# USB_Audio_Interface.net
KiCad netlist of a schematic drawn in EAGLE
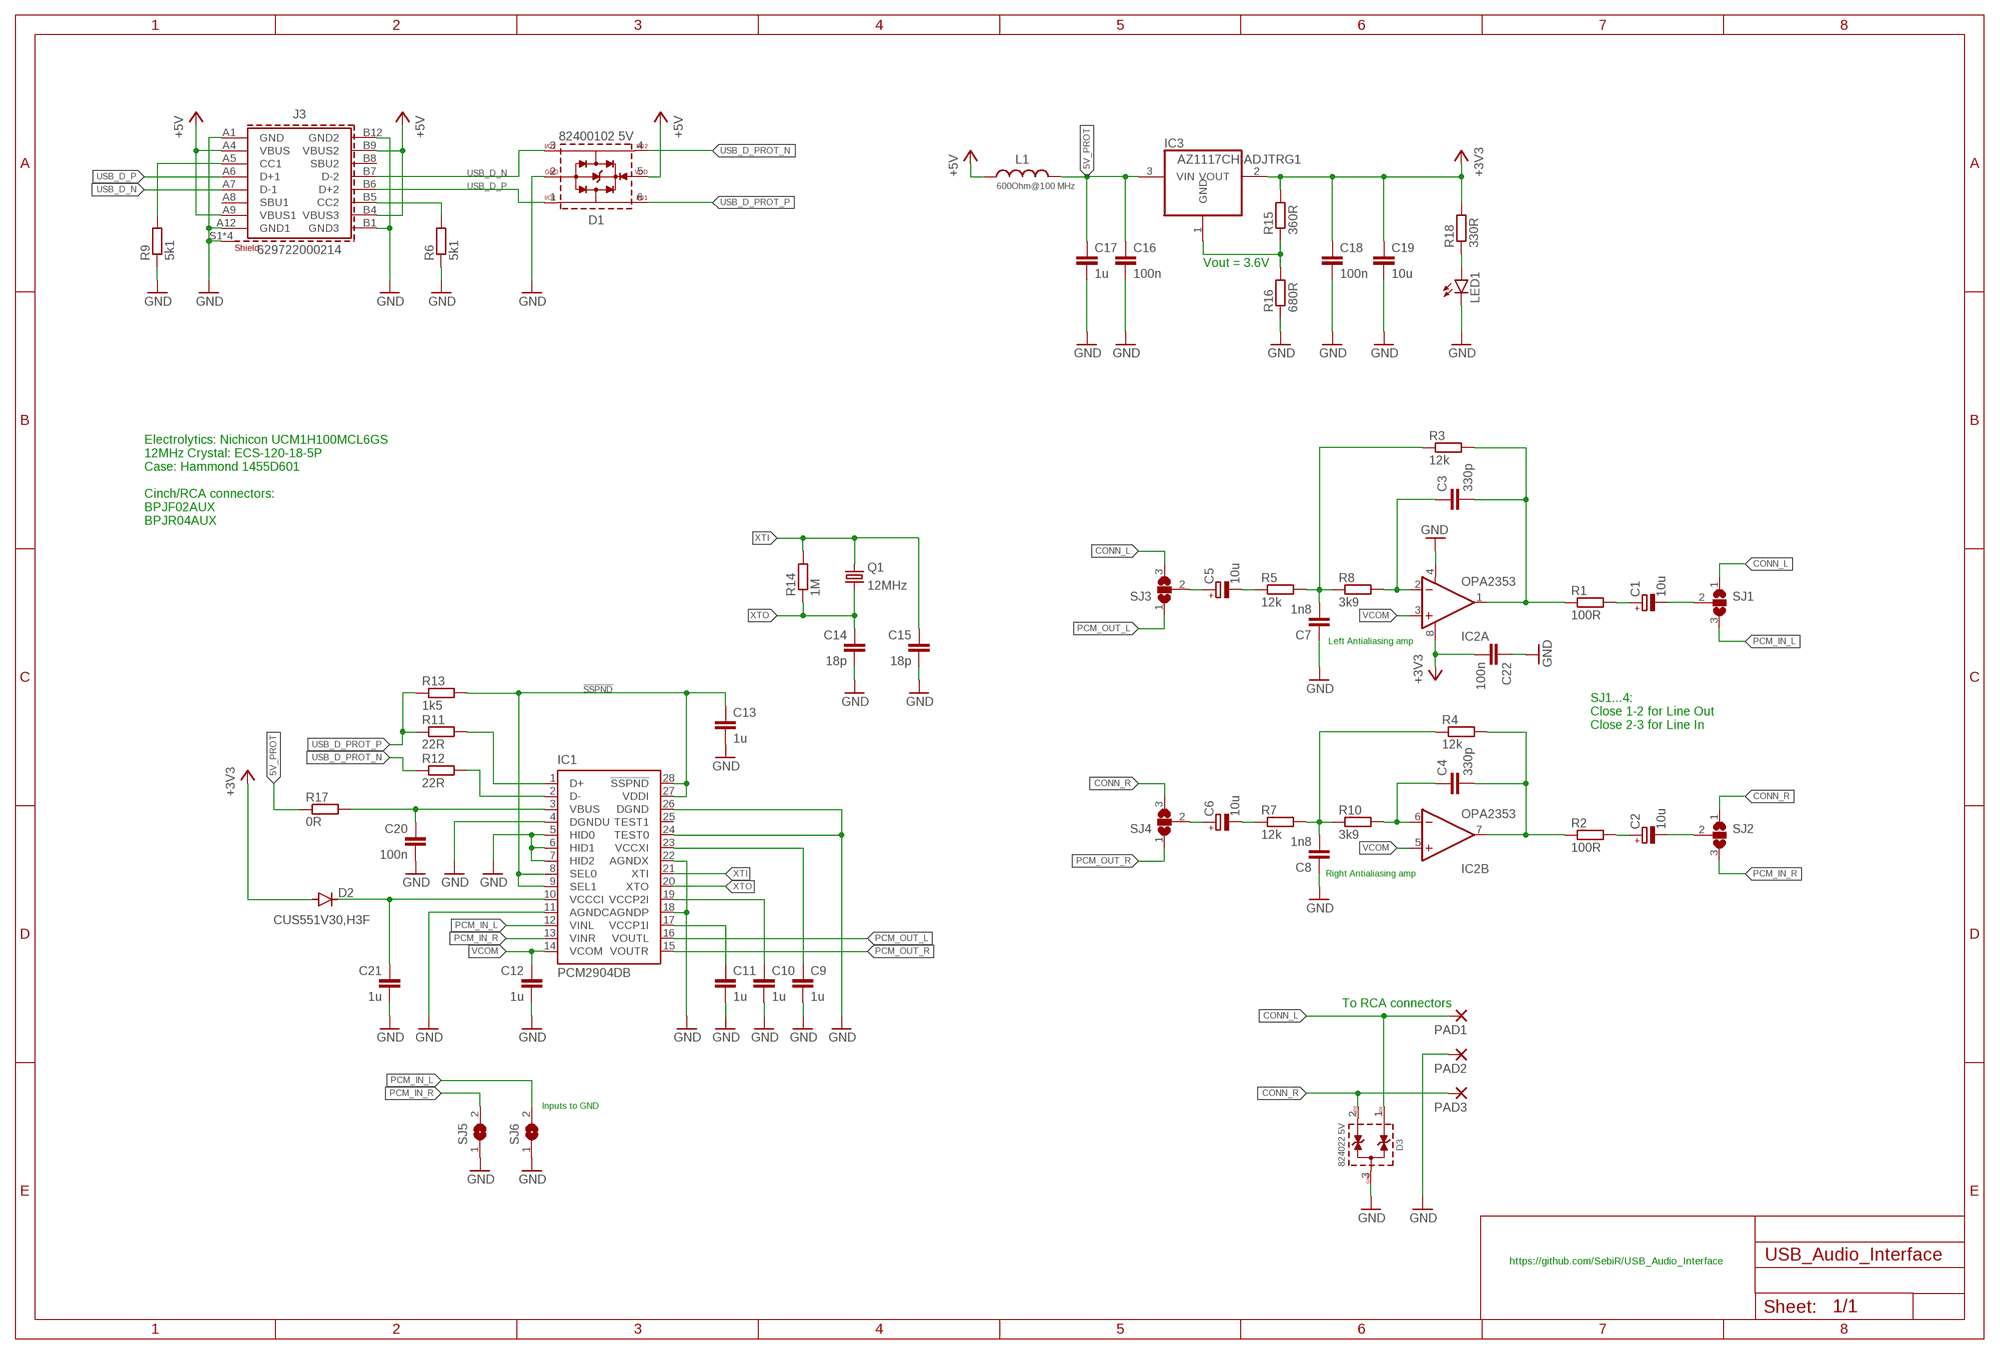
[diagram p0: schematic, sheet 1]

(export (version "E")
  (design (tool "Eeschema 10.0.6"))
  (components
    (comp (ref "C1")
      (value "10u")
      (footprint "eagle-import:UD-4X5,8_NICHICON")
      (libsource (lib "eagle-import") (part "CPOL-EUUD-4X5,8"))
    )
    (comp (ref "C2")
      (value "10u")
      (footprint "eagle-import:UD-4X5,8_NICHICON")
      (libsource (lib "eagle-import") (part "CPOL-EUUD-4X5,8"))
    )
    (comp (ref "C3")
      (value "330p")
      (footprint "eagle-import:C0603")
      (libsource (lib "eagle-import") (part "C-EUC0603"))
    )
    (comp (ref "C4")
      (value "330p")
      (footprint "eagle-import:C0603")
      (libsource (lib "eagle-import") (part "C-EUC0603"))
    )
    (comp (ref "C5")
      (value "10u")
      (footprint "eagle-import:UD-4X5,8_NICHICON")
      (libsource (lib "eagle-import") (part "CPOL-EUUD-4X5,8"))
    )
    (comp (ref "C6")
      (value "10u")
      (footprint "eagle-import:UD-4X5,8_NICHICON")
      (libsource (lib "eagle-import") (part "CPOL-EUUD-4X5,8"))
    )
    (comp (ref "C7")
      (value "1n8")
      (footprint "eagle-import:C0603")
      (libsource (lib "eagle-import") (part "C-EUC0603"))
    )
    (comp (ref "C8")
      (value "1n8")
      (footprint "eagle-import:C0603")
      (libsource (lib "eagle-import") (part "C-EUC0603"))
    )
    (comp (ref "C9")
      (value "1u")
      (footprint "eagle-import:C0603")
      (libsource (lib "eagle-import") (part "C-EUC0603"))
    )
    (comp (ref "C10")
      (value "1u")
      (footprint "eagle-import:C0603")
      (libsource (lib "eagle-import") (part "C-EUC0603"))
    )
    (comp (ref "C11")
      (value "1u")
      (footprint "eagle-import:C0603")
      (libsource (lib "eagle-import") (part "C-EUC0603"))
    )
    (comp (ref "C12")
      (value "1u")
      (footprint "eagle-import:C0603")
      (libsource (lib "eagle-import") (part "C-EUC0603"))
    )
    (comp (ref "C13")
      (value "1u")
      (footprint "eagle-import:C0603")
      (libsource (lib "eagle-import") (part "C-EUC0603"))
    )
    (comp (ref "C14")
      (value "18p")
      (footprint "eagle-import:C0603")
      (libsource (lib "eagle-import") (part "C-EUC0603"))
    )
    (comp (ref "C15")
      (value "18p")
      (footprint "eagle-import:C0603")
      (libsource (lib "eagle-import") (part "C-EUC0603"))
    )
    (comp (ref "C16")
      (value "100n")
      (footprint "eagle-import:C0603")
      (libsource (lib "eagle-import") (part "C-EUC0603"))
    )
    (comp (ref "C17")
      (value "1u")
      (footprint "eagle-import:C0603")
      (libsource (lib "eagle-import") (part "C-EUC0603"))
    )
    (comp (ref "C18")
      (value "100n")
      (footprint "eagle-import:C0603")
      (libsource (lib "eagle-import") (part "C-EUC0603"))
    )
    (comp (ref "C19")
      (value "10u")
      (footprint "eagle-import:C0603")
      (libsource (lib "eagle-import") (part "C-EUC0603"))
    )
    (comp (ref "C20")
      (value "100n")
      (footprint "eagle-import:C0603")
      (libsource (lib "eagle-import") (part "C-EUC0603"))
    )
    (comp (ref "C21")
      (value "1u")
      (footprint "eagle-import:C0603")
      (libsource (lib "eagle-import") (part "C-EUC0603"))
    )
    (comp (ref "C22")
      (value "100n")
      (footprint "eagle-import:C0603")
      (libsource (lib "eagle-import") (part "C-EUC0603"))
    )
    (comp (ref "D1")
      (value "82400102 5V")
      (footprint "eagle-import:WE-TVS_SOT23-6L")
      (libsource (lib "eagle-import") (part "WE-TVS-HS_SOT23-6L_82400102"))
    )
    (comp (ref "D2")
      (value "CUS551V30,H3F")
      (footprint "eagle-import:SOD323-R")
      (libsource (lib "eagle-import") (part "DIODE-SOD323-R"))
    )
    (comp (ref "D3")
      (value "824022 5V")
      (footprint "eagle-import:WE-TVS_SOT23-3L")
      (libsource (lib "eagle-import") (part "WE-TVS_SOT23-3L_824022"))
    )
    (comp (ref "IC1")
      (value "PCM2904DB")
      (footprint "eagle-import:SSOP28DB")
      (fields (field (name "MF") "TEXAS INSTRUMENT CONNECTORS"))
      (libsource (lib "eagle-import") (part "PCM2904DB"))
    )
    (comp (ref "IC2")
      (value "OPA2353")
      (footprint "eagle-import:SO08")
      (fields (field (name "MANUFACTURER") "TEXAS INSTRUMENTS") (field (name "MPN") "OPA2340UA"))
      (libsource (lib "eagle-import") (part "OPA2340U"))
    )
    (comp (ref "IC3")
      (value "AZ1117CH-ADJTRG1")
      (footprint "eagle-import:SOT223")
      (fields (field (name "MPN") "REG1117"))
      (libsource (lib "eagle-import") (part "REG1117"))
    )
    (comp (ref "J3")
      (value "629722000214")
      (footprint "eagle-import:629722000214")
      (libsource (lib "eagle-import") (part "629722000214"))
    )
    (comp (ref "L1")
      (value "600Ohm@100 MHz")
      (footprint "eagle-import:WE-CBF_0603_W2.6")
      (libsource (lib "eagle-import") (part "WE-CBF_0603_HC_742792651"))
    )
    (comp (ref "LED1")
      (value "LEDMICRO-SIDELED")
      (footprint "eagle-import:MICRO-SIDELED")
      (libsource (lib "eagle-import") (part "LEDMICRO-SIDELED"))
    )
    (comp (ref "PAD1")
      (value "2,15/1,0")
      (footprint "eagle-import:2,15_1,0")
      (libsource (lib "eagle-import") (part "2,15/1,0"))
    )
    (comp (ref "PAD2")
      (value "2,15/1,0")
      (footprint "eagle-import:2,15_1,0")
      (libsource (lib "eagle-import") (part "2,15/1,0"))
    )
    (comp (ref "PAD3")
      (value "2,15/1,0")
      (footprint "eagle-import:2,15_1,0")
      (libsource (lib "eagle-import") (part "2,15/1,0"))
    )
    (comp (ref "Q1")
      (value "12MHz")
      (footprint "eagle-import:HC49UP")
      (libsource (lib "eagle-import") (part "CRYSTALHC49UP"))
    )
    (comp (ref "R1")
      (value "100R")
      (footprint "eagle-import:R0603")
      (libsource (lib "eagle-import") (part "R-EU_R0603"))
    )
    (comp (ref "R2")
      (value "100R")
      (footprint "eagle-import:R0603")
      (libsource (lib "eagle-import") (part "R-EU_R0603"))
    )
    (comp (ref "R3")
      (value "12k")
      (footprint "eagle-import:R0603")
      (libsource (lib "eagle-import") (part "R-EU_R0603"))
    )
    (comp (ref "R4")
      (value "12k")
      (footprint "eagle-import:R0603")
      (libsource (lib "eagle-import") (part "R-EU_R0603"))
    )
    (comp (ref "R5")
      (value "12k")
      (footprint "eagle-import:R0603")
      (libsource (lib "eagle-import") (part "R-EU_R0603"))
    )
    (comp (ref "R6")
      (value "5k1")
      (footprint "eagle-import:R0603")
      (libsource (lib "eagle-import") (part "R-EU_R0603"))
    )
    (comp (ref "R7")
      (value "12k")
      (footprint "eagle-import:R0603")
      (libsource (lib "eagle-import") (part "R-EU_R0603"))
    )
    (comp (ref "R8")
      (value "3k9")
      (footprint "eagle-import:R0603")
      (libsource (lib "eagle-import") (part "R-EU_R0603"))
    )
    (comp (ref "R9")
      (value "5k1")
      (footprint "eagle-import:R0603")
      (libsource (lib "eagle-import") (part "R-EU_R0603"))
    )
    (comp (ref "R10")
      (value "3k9")
      (footprint "eagle-import:R0603")
      (libsource (lib "eagle-import") (part "R-EU_R0603"))
    )
    (comp (ref "R11")
      (value "22R")
      (footprint "eagle-import:R0603")
      (libsource (lib "eagle-import") (part "R-EU_R0603"))
    )
    (comp (ref "R12")
      (value "22R")
      (footprint "eagle-import:R0603")
      (libsource (lib "eagle-import") (part "R-EU_R0603"))
    )
    (comp (ref "R13")
      (value "1k5")
      (footprint "eagle-import:R0603")
      (libsource (lib "eagle-import") (part "R-EU_R0603"))
    )
    (comp (ref "R14")
      (value "1M")
      (footprint "eagle-import:R0603")
      (libsource (lib "eagle-import") (part "R-EU_R0603"))
    )
    (comp (ref "R15")
      (value "360R")
      (footprint "eagle-import:R0603")
      (libsource (lib "eagle-import") (part "R-EU_R0603"))
    )
    (comp (ref "R16")
      (value "680R")
      (footprint "eagle-import:R0603")
      (libsource (lib "eagle-import") (part "R-EU_R0603"))
    )
    (comp (ref "R17")
      (value "0R")
      (footprint "eagle-import:R0603")
      (libsource (lib "eagle-import") (part "R-EU_R0603"))
    )
    (comp (ref "R18")
      (value "330R")
      (footprint "eagle-import:R0603")
      (libsource (lib "eagle-import") (part "R-EU_R0603"))
    )
    (comp (ref "SJ1")
      (value "SJ2W")
      (footprint "eagle-import:SJ_2")
      (libsource (lib "eagle-import") (part "SJ2W"))
    )
    (comp (ref "SJ2")
      (value "SJ2W")
      (footprint "eagle-import:SJ_2")
      (libsource (lib "eagle-import") (part "SJ2W"))
    )
    (comp (ref "SJ3")
      (value "SJ2W")
      (footprint "eagle-import:SJ_2")
      (libsource (lib "eagle-import") (part "SJ2W"))
    )
    (comp (ref "SJ4")
      (value "SJ2W")
      (footprint "eagle-import:SJ_2")
      (libsource (lib "eagle-import") (part "SJ2W"))
    )
    (comp (ref "SJ5") (value "SJ") (footprint "eagle-import:SJ") (libsource (lib "eagle-import") (part "SJ")))
    (comp (ref "SJ6") (value "SJ") (footprint "eagle-import:SJ") (libsource (lib "eagle-import") (part "SJ")))
  )
  (nets
    (net (code "1") (name "+3V3") (class "Default")
      (node (ref "C18") (pin "1") (pinfunction "1_1") (pintype "passive"))
      (node (ref "C19") (pin "1") (pinfunction "1_1") (pintype "passive"))
      (node (ref "C22") (pin "2") (pinfunction "2_2") (pintype "passive"))
      (node (ref "D2") (pin "A") (pinfunction "A_A") (pintype "passive"))
      (node (ref "IC2") (pin "8") (pinfunction "V+_8") (pintype "power_in"))
      (node (ref "IC3") (pin "2") (pinfunction "VOUT_2") (pintype "output"))
      (node (ref "R15") (pin "2") (pinfunction "2_2") (pintype "passive"))
      (node (ref "R18") (pin "2") (pinfunction "2_2") (pintype "passive"))
    )
    (net (code "2") (name "+5V") (class "Default")
      (node (ref "D1") (pin "5") (pinfunction "VDD_5") (pintype "passive"))
      (node (ref "J3") (pin "A4") (pinfunction "VBUS_A4") (pintype "passive"))
      (node (ref "J3") (pin "A9") (pinfunction "VBUS1_A9") (pintype "passive"))
      (node (ref "J3") (pin "B4") (pinfunction "VBUS3_B4") (pintype "passive"))
      (node (ref "J3") (pin "B9") (pinfunction "VBUS2_B9") (pintype "passive"))
      (node (ref "L1") (pin "1") (pinfunction "1_1") (pintype "passive"))
    )
    (net (code "3") (name "/~{SSPND}") (class "Default")
      (node (ref "C13") (pin "1") (pinfunction "1_1") (pintype "passive"))
      (node (ref "IC1") (pin "27") (pinfunction "VDDI_27") (pintype "power_in"))
      (node (ref "IC1") (pin "28") (pinfunction "~{SSPND}_28") (pintype "output"))
      (node (ref "IC1") (pin "8") (pinfunction "SEL0_8") (pintype "input"))
      (node (ref "IC1") (pin "9") (pinfunction "SEL1_9") (pintype "input"))
      (node (ref "R13") (pin "2") (pinfunction "2_2") (pintype "passive"))
    )
    (net (code "4") (name "5V_PROT") (class "Default")
      (node (ref "C16") (pin "1") (pinfunction "1_1") (pintype "passive"))
      (node (ref "C17") (pin "1") (pinfunction "1_1") (pintype "passive"))
      (node (ref "IC3") (pin "3") (pinfunction "VIN_3") (pintype "input"))
      (node (ref "L1") (pin "2") (pinfunction "2_2") (pintype "passive"))
      (node (ref "R17") (pin "1") (pinfunction "1_1") (pintype "passive"))
    )
    (net (code "5") (name "CONN_L") (class "Default")
      (node (ref "D3") (pin "1") (pinfunction "I/O1_1") (pintype "passive"))
      (node (ref "PAD1") (pin "1") (pinfunction "P_1") (pintype "passive"))
      (node (ref "SJ1") (pin "1") (pinfunction "1_1") (pintype "passive"))
      (node (ref "SJ3") (pin "3") (pinfunction "3_3") (pintype "passive"))
    )
    (net (code "6") (name "CONN_R") (class "Default")
      (node (ref "D3") (pin "2") (pinfunction "I/O2_2") (pintype "passive"))
      (node (ref "PAD3") (pin "1") (pinfunction "P_1") (pintype "passive"))
      (node (ref "SJ2") (pin "1") (pinfunction "1_1") (pintype "passive"))
      (node (ref "SJ4") (pin "3") (pinfunction "3_3") (pintype "passive"))
    )
    (net (code "7") (name "GND") (class "Default")
      (node (ref "C10") (pin "2") (pinfunction "2_2") (pintype "passive"))
      (node (ref "C11") (pin "2") (pinfunction "2_2") (pintype "passive"))
      (node (ref "C12") (pin "2") (pinfunction "2_2") (pintype "passive"))
      (node (ref "C13") (pin "2") (pinfunction "2_2") (pintype "passive"))
      (node (ref "C14") (pin "2") (pinfunction "2_2") (pintype "passive"))
      (node (ref "C15") (pin "2") (pinfunction "2_2") (pintype "passive"))
      (node (ref "C16") (pin "2") (pinfunction "2_2") (pintype "passive"))
      (node (ref "C17") (pin "2") (pinfunction "2_2") (pintype "passive"))
      (node (ref "C18") (pin "2") (pinfunction "2_2") (pintype "passive"))
      (node (ref "C19") (pin "2") (pinfunction "2_2") (pintype "passive"))
      (node (ref "C20") (pin "2") (pinfunction "2_2") (pintype "passive"))
      (node (ref "C21") (pin "2") (pinfunction "2_2") (pintype "passive"))
      (node (ref "C22") (pin "1") (pinfunction "1_1") (pintype "passive"))
      (node (ref "C7") (pin "1") (pinfunction "1_1") (pintype "passive"))
      (node (ref "C8") (pin "1") (pinfunction "1_1") (pintype "passive"))
      (node (ref "C9") (pin "2") (pinfunction "2_2") (pintype "passive"))
      (node (ref "D1") (pin "2") (pinfunction "GND_2") (pintype "passive"))
      (node (ref "D3") (pin "3") (pinfunction "GND_3") (pintype "passive"))
      (node (ref "IC1") (pin "11") (pinfunction "AGNDC_11") (pintype "power_in"))
      (node (ref "IC1") (pin "18") (pinfunction "AGNDP_18") (pintype "power_in"))
      (node (ref "IC1") (pin "22") (pinfunction "AGNDX_22") (pintype "power_in"))
      (node (ref "IC1") (pin "24") (pinfunction "TEST0_24") (pintype "input"))
      (node (ref "IC1") (pin "26") (pinfunction "DGND_26") (pintype "power_in"))
      (node (ref "IC1") (pin "4") (pinfunction "DGNDU_4") (pintype "power_in"))
      (node (ref "IC1") (pin "5") (pinfunction "HID0_5") (pintype "input"))
      (node (ref "IC1") (pin "6") (pinfunction "HID1_6") (pintype "input"))
      (node (ref "IC1") (pin "7") (pinfunction "HID2_7") (pintype "input"))
      (node (ref "IC2") (pin "4") (pinfunction "V-_4") (pintype "power_in"))
      (node (ref "J3") (pin "A1") (pinfunction "GND_A1") (pintype "passive"))
      (node (ref "J3") (pin "A12") (pinfunction "GND1_A12") (pintype "passive"))
      (node (ref "J3") (pin "B1") (pinfunction "GND3_B1") (pintype "passive"))
      (node (ref "J3") (pin "B12") (pinfunction "GND2_B12") (pintype "passive"))
      (node (ref "J3") (pin "S1") (pinfunction "SHIELD_S1") (pintype "passive"))
      (node (ref "J3") (pin "S2") (pinfunction "SHIELD_S2") (pintype "passive"))
      (node (ref "J3") (pin "S3") (pinfunction "SHIELD_S3") (pintype "passive"))
      (node (ref "J3") (pin "S4") (pinfunction "SHIELD_S4") (pintype "passive"))
      (node (ref "LED1") (pin "C") (pinfunction "C_C") (pintype "passive"))
      (node (ref "PAD2") (pin "1") (pinfunction "P_1") (pintype "passive"))
      (node (ref "R16") (pin "1") (pinfunction "1_1") (pintype "passive"))
      (node (ref "R6") (pin "1") (pinfunction "1_1") (pintype "passive"))
      (node (ref "R9") (pin "1") (pinfunction "1_1") (pintype "passive"))
      (node (ref "SJ5") (pin "1") (pinfunction "1_1") (pintype "passive"))
      (node (ref "SJ6") (pin "1") (pinfunction "1_1") (pintype "passive"))
    )
    (net (code "8") (name "Net-(C1-Pad+)") (class "Default")
      (node (ref "C1") (pin "+") (pinfunction "+_+") (pintype "passive"))
      (node (ref "R1") (pin "2") (pinfunction "2_2") (pintype "passive"))
    )
    (net (code "9") (name "Net-(C1-Pad-)") (class "Default")
      (node (ref "C1") (pin "-") (pinfunction "-_-") (pintype "passive"))
      (node (ref "SJ1") (pin "2") (pinfunction "2_2") (pintype "passive"))
    )
    (net (code "10") (name "Net-(C2-Pad+)") (class "Default")
      (node (ref "C2") (pin "+") (pinfunction "+_+") (pintype "passive"))
      (node (ref "R2") (pin "2") (pinfunction "2_2") (pintype "passive"))
    )
    (net (code "11") (name "Net-(C2-Pad-)") (class "Default")
      (node (ref "C2") (pin "-") (pinfunction "-_-") (pintype "passive"))
      (node (ref "SJ2") (pin "2") (pinfunction "2_2") (pintype "passive"))
    )
    (net (code "12") (name "Net-(C5-Pad+)") (class "Default")
      (node (ref "C5") (pin "+") (pinfunction "+_+") (pintype "passive"))
      (node (ref "SJ3") (pin "2") (pinfunction "2_2") (pintype "passive"))
    )
    (net (code "13") (name "Net-(C5-Pad-)") (class "Default")
      (node (ref "C5") (pin "-") (pinfunction "-_-") (pintype "passive"))
      (node (ref "R5") (pin "1") (pinfunction "1_1") (pintype "passive"))
    )
    (net (code "14") (name "Net-(C6-Pad+)") (class "Default")
      (node (ref "C6") (pin "+") (pinfunction "+_+") (pintype "passive"))
      (node (ref "SJ4") (pin "2") (pinfunction "2_2") (pintype "passive"))
    )
    (net (code "15") (name "Net-(C6-Pad-)") (class "Default")
      (node (ref "C6") (pin "-") (pinfunction "-_-") (pintype "passive"))
      (node (ref "R7") (pin "1") (pinfunction "1_1") (pintype "passive"))
    )
    (net (code "16") (name "Net-(C7-Pad2)") (class "Default")
      (node (ref "C7") (pin "2") (pinfunction "2_2") (pintype "passive"))
      (node (ref "R3") (pin "1") (pinfunction "1_1") (pintype "passive"))
      (node (ref "R5") (pin "2") (pinfunction "2_2") (pintype "passive"))
      (node (ref "R8") (pin "1") (pinfunction "1_1") (pintype "passive"))
    )
    (net (code "17") (name "Net-(C8-Pad2)") (class "Default")
      (node (ref "C8") (pin "2") (pinfunction "2_2") (pintype "passive"))
      (node (ref "R10") (pin "1") (pinfunction "1_1") (pintype "passive"))
      (node (ref "R4") (pin "1") (pinfunction "1_1") (pintype "passive"))
      (node (ref "R7") (pin "2") (pinfunction "2_2") (pintype "passive"))
    )
    (net (code "18") (name "Net-(IC1-D+)") (class "Default")
      (node (ref "IC1") (pin "1") (pinfunction "D+_1") (pintype "bidirectional"))
      (node (ref "R11") (pin "2") (pinfunction "2_2") (pintype "passive"))
    )
    (net (code "19") (name "Net-(IC1-D-)") (class "Default")
      (node (ref "IC1") (pin "2") (pinfunction "D-_2") (pintype "bidirectional"))
      (node (ref "R12") (pin "2") (pinfunction "2_2") (pintype "passive"))
    )
    (net (code "20") (name "Net-(IC1-VBUS)") (class "Default")
      (node (ref "C20") (pin "1") (pinfunction "1_1") (pintype "passive"))
      (node (ref "IC1") (pin "3") (pinfunction "VBUS_3") (pintype "power_in"))
      (node (ref "R17") (pin "2") (pinfunction "2_2") (pintype "passive"))
    )
    (net (code "21") (name "Net-(IC1-VCCCI)") (class "Default")
      (node (ref "C21") (pin "1") (pinfunction "1_1") (pintype "passive"))
      (node (ref "D2") (pin "C") (pinfunction "C_C") (pintype "passive"))
      (node (ref "IC1") (pin "10") (pinfunction "VCCCI_10") (pintype "power_in"))
    )
    (net (code "22") (name "Net-(IC1-VCCP1I)") (class "Default")
      (node (ref "C11") (pin "1") (pinfunction "1_1") (pintype "passive"))
      (node (ref "IC1") (pin "17") (pinfunction "VCCP1I_17") (pintype "input"))
    )
    (net (code "23") (name "Net-(IC1-VCCP2I)") (class "Default")
      (node (ref "C10") (pin "1") (pinfunction "1_1") (pintype "passive"))
      (node (ref "IC1") (pin "19") (pinfunction "VCCP2I_19") (pintype "power_in"))
    )
    (net (code "24") (name "Net-(IC1-VCCXI)") (class "Default")
      (node (ref "C9") (pin "1") (pinfunction "1_1") (pintype "passive"))
      (node (ref "IC1") (pin "23") (pinfunction "VCCXI_23") (pintype "power_in"))
    )
    (net (code "25") (name "Net-(IC2A--IN)") (class "Default")
      (node (ref "C3") (pin "1") (pinfunction "1_1") (pintype "passive"))
      (node (ref "IC2") (pin "2") (pinfunction "-IN_2") (pintype "input"))
      (node (ref "R8") (pin "2") (pinfunction "2_2") (pintype "passive"))
    )
    (net (code "26") (name "Net-(IC2A-OUT)") (class "Default")
      (node (ref "C3") (pin "2") (pinfunction "2_2") (pintype "passive"))
      (node (ref "IC2") (pin "1") (pinfunction "OUT_1") (pintype "output"))
      (node (ref "R1") (pin "1") (pinfunction "1_1") (pintype "passive"))
      (node (ref "R3") (pin "2") (pinfunction "2_2") (pintype "passive"))
    )
    (net (code "27") (name "Net-(IC2B--IN)") (class "Default")
      (node (ref "C4") (pin "1") (pinfunction "1_1") (pintype "passive"))
      (node (ref "IC2") (pin "6") (pinfunction "-IN_6") (pintype "input"))
      (node (ref "R10") (pin "2") (pinfunction "2_2") (pintype "passive"))
    )
    (net (code "28") (name "Net-(IC2B-OUT)") (class "Default")
      (node (ref "C4") (pin "2") (pinfunction "2_2") (pintype "passive"))
      (node (ref "IC2") (pin "7") (pinfunction "OUT_7") (pintype "output"))
      (node (ref "R2") (pin "1") (pinfunction "1_1") (pintype "passive"))
      (node (ref "R4") (pin "2") (pinfunction "2_2") (pintype "passive"))
    )
    (net (code "29") (name "Net-(IC3-GND)") (class "Default")
      (node (ref "IC3") (pin "1") (pinfunction "GND_1") (pintype "power_in"))
      (node (ref "R15") (pin "1") (pinfunction "1_1") (pintype "passive"))
      (node (ref "R16") (pin "2") (pinfunction "2_2") (pintype "passive"))
    )
    (net (code "30") (name "Net-(J3-CC1)") (class "Default")
      (node (ref "J3") (pin "A5") (pinfunction "CC1_A5") (pintype "passive"))
      (node (ref "R9") (pin "2") (pinfunction "2_2") (pintype "passive"))
    )
    (net (code "31") (name "Net-(J3-CC2)") (class "Default")
      (node (ref "J3") (pin "B5") (pinfunction "CC2_B5") (pintype "passive"))
      (node (ref "R6") (pin "2") (pinfunction "2_2") (pintype "passive"))
    )
    (net (code "32") (name "Net-(LED1-PadA)") (class "Default")
      (node (ref "LED1") (pin "A") (pinfunction "A_A") (pintype "passive"))
      (node (ref "R18") (pin "1") (pinfunction "1_1") (pintype "passive"))
    )
    (net (code "33") (name "PCM_IN_L") (class "Default")
      (node (ref "IC1") (pin "12") (pinfunction "VINL_12") (pintype "input"))
      (node (ref "SJ1") (pin "3") (pinfunction "3_3") (pintype "passive"))
      (node (ref "SJ6") (pin "2") (pinfunction "2_2") (pintype "passive"))
    )
    (net (code "34") (name "PCM_IN_R") (class "Default")
      (node (ref "IC1") (pin "13") (pinfunction "VINR_13") (pintype "input"))
      (node (ref "SJ2") (pin "3") (pinfunction "3_3") (pintype "passive"))
      (node (ref "SJ5") (pin "2") (pinfunction "2_2") (pintype "passive"))
    )
    (net (code "35") (name "PCM_OUT_L") (class "Default")
      (node (ref "IC1") (pin "16") (pinfunction "VOUTL_16") (pintype "output"))
      (node (ref "SJ3") (pin "1") (pinfunction "1_1") (pintype "passive"))
    )
    (net (code "36") (name "PCM_OUT_R") (class "Default")
      (node (ref "IC1") (pin "15") (pinfunction "VOUTR_15") (pintype "output"))
      (node (ref "SJ4") (pin "1") (pinfunction "1_1") (pintype "passive"))
    )
    (net (code "37") (name "USB_D_N") (class "Default")
      (node (ref "D1") (pin "3") (pinfunction "I/O2_3") (pintype "passive"))
      (node (ref "J3") (pin "A7") (pinfunction "D-1_A7") (pintype "passive"))
      (node (ref "J3") (pin "B7") (pinfunction "D-2_B7") (pintype "passive"))
    )
    (net (code "38") (name "USB_D_P") (class "Default")
      (node (ref "D1") (pin "1") (pinfunction "I/O1_1") (pintype "passive"))
      (node (ref "J3") (pin "A6") (pinfunction "D+1_A6") (pintype "passive"))
      (node (ref "J3") (pin "B6") (pinfunction "D+2_B6") (pintype "passive"))
    )
    (net (code "39") (name "USB_D_PROT_N") (class "Default")
      (node (ref "D1") (pin "4") (pinfunction "I/O4_4") (pintype "passive"))
      (node (ref "R12") (pin "1") (pinfunction "1_1") (pintype "passive"))
    )
    (net (code "40") (name "USB_D_PROT_P") (class "Default")
      (node (ref "D1") (pin "6") (pinfunction "I/O3_6") (pintype "passive"))
      (node (ref "R11") (pin "1") (pinfunction "1_1") (pintype "passive"))
      (node (ref "R13") (pin "1") (pinfunction "1_1") (pintype "passive"))
    )
    (net (code "41") (name "VCOM") (class "Default")
      (node (ref "C12") (pin "1") (pinfunction "1_1") (pintype "passive"))
      (node (ref "IC1") (pin "14") (pinfunction "VCOM_14") (pintype "power_in"))
      (node (ref "IC2") (pin "3") (pinfunction "+IN_3") (pintype "input"))
      (node (ref "IC2") (pin "5") (pinfunction "+IN_5") (pintype "input"))
    )
    (net (code "42") (name "XTI") (class "Default")
      (node (ref "C15") (pin "1") (pinfunction "1_1") (pintype "passive"))
      (node (ref "IC1") (pin "21") (pinfunction "XTI_21") (pintype "input"))
      (node (ref "Q1") (pin "2") (pinfunction "2_2") (pintype "passive"))
      (node (ref "R14") (pin "2") (pinfunction "2_2") (pintype "passive"))
    )
    (net (code "43") (name "XTO") (class "Default")
      (node (ref "C14") (pin "1") (pinfunction "1_1") (pintype "passive"))
      (node (ref "IC1") (pin "20") (pinfunction "XTO_20") (pintype "output"))
      (node (ref "Q1") (pin "1") (pinfunction "1_1") (pintype "passive"))
      (node (ref "R14") (pin "1") (pinfunction "1_1") (pintype "passive"))
    )
    (net (code "44") (name "unconnected-(IC1-TEST1-Pad25)") (class "Default")
      (node (ref "IC1") (pin "25") (pinfunction "TEST1_25") (pintype "output"))
    )
    (net (code "45") (name "unconnected-(J3-SBU1-PadA8)") (class "Default")
      (node (ref "J3") (pin "A8") (pinfunction "SBU1_A8") (pintype "passive"))
    )
    (net (code "46") (name "unconnected-(J3-SBU2-PadB8)") (class "Default")
      (node (ref "J3") (pin "B8") (pinfunction "SBU2_B8") (pintype "passive"))
    )
  )
)
